# Detector.net
KiCad netlist of a schematic drawn in Altium Designer
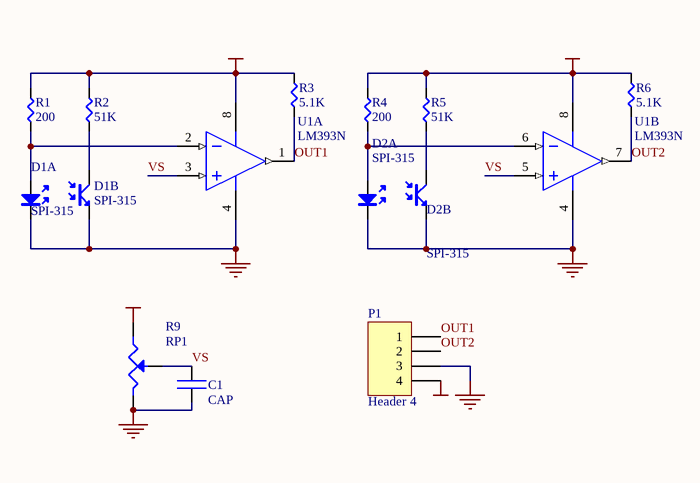
[diagram p0: Detector.SchDoc]

(export (version "E")
  (design (tool "Eeschema 10.0.6"))
  (components
    (comp (ref "C1") (value "CAP") (footprint "C0.1/0.2") (libsource (lib "Traffic_light") (part "CAP")))
    (comp (ref "D1")
      (value "SPI-315")
      (footprint "photodevice")
      (libsource (lib "Traffic_light") (part "PHOTOISO3"))
    )
    (comp (ref "D2")
      (value "SPI-315")
      (footprint "photodevice")
      (libsource (lib "Traffic_light") (part "PHOTOISO3"))
    )
    (comp (ref "P1")
      (value "Header 4")
      (footprint "HDR1X4")
      (description "Header, 4-Pin")
      (fields (field (name "PUBLISHER") "Altium Limited"))
      (libsource (lib "Miscellaneous Connectors") (part "Header 4"))
    )
    (comp (ref "R1") (value "200") (footprint "AXIAL0.4") (libsource (lib "Traffic_light") (part "R1")))
    (comp (ref "R2") (value "51K") (footprint "AXIAL0.4") (libsource (lib "Traffic_light") (part "R1")))
    (comp (ref "R3") (value "5.1K") (footprint "AXIAL0.4") (libsource (lib "Traffic_light") (part "R1")))
    (comp (ref "R4") (value "200") (footprint "AXIAL0.4") (libsource (lib "Traffic_light") (part "R1")))
    (comp (ref "R5") (value "51K") (footprint "AXIAL0.4") (libsource (lib "Traffic_light") (part "R1")))
    (comp (ref "R6") (value "5.1K") (footprint "AXIAL0.4") (libsource (lib "Traffic_light") (part "R1")))
    (comp (ref "R9")
      (value "RP1")
      (footprint "RP_05")
      (description "Potentiometer")
      (libsource (lib "Traffic_light") (part "RP1"))
    )
    (comp (ref "U1")
      (value "LM393N")
      (footprint "626-05")
      (description "Dual Comparator")
      (fields (field (name "PUBLISHER") "Altium Limited"))
      (libsource (lib "Motorola Analog Comparator") (part "LM393N"))
    )
  )
  (nets
    (net (code "1") (name "/OUT1") (class "Default")
      (node (ref "P1") (pin "1") (pinfunction "1_1") (pintype "passive"))
      (node (ref "R3") (pin "1") (pintype "passive"))
      (node (ref "U1") (pin "1") (pinfunction "OUT_1") (pintype "output"))
    )
    (net (code "2") (name "/OUT2") (class "Default")
      (node (ref "P1") (pin "2") (pinfunction "2_2") (pintype "passive"))
      (node (ref "R6") (pin "1") (pintype "passive"))
      (node (ref "U1") (pin "7") (pinfunction "OUT_7") (pintype "output"))
    )
    (net (code "3") (name "/VS") (class "Default")
      (node (ref "C1") (pin "1") (pintype "passive"))
      (node (ref "R9") (pin "2") (pinfunction "W_2") (pintype "passive"))
      (node (ref "U1") (pin "3") (pinfunction "IN+_3") (pintype "input"))
      (node (ref "U1") (pin "5") (pinfunction "IN+_5") (pintype "input"))
    )
    (net (code "4") (name "GND") (class "Default")
      (node (ref "C1") (pin "2") (pintype "passive"))
      (node (ref "D1") (pin "2") (pintype "passive"))
      (node (ref "D1") (pin "4") (pintype "passive"))
      (node (ref "D2") (pin "2") (pintype "passive"))
      (node (ref "D2") (pin "4") (pintype "passive"))
      (node (ref "P1") (pin "3") (pinfunction "3_3") (pintype "passive"))
      (node (ref "R9") (pin "1") (pinfunction "1_1") (pintype "passive"))
      (node (ref "U1") (pin "4") (pinfunction "GND_4") (pintype "power_in"))
    )
    (net (code "5") (name "Net-(D1-Pad3)") (class "Default")
      (node (ref "D1") (pin "3") (pintype "passive"))
      (node (ref "R2") (pin "1") (pintype "passive"))
    )
    (net (code "6") (name "Net-(D2-Pad3)") (class "Default")
      (node (ref "D2") (pin "3") (pintype "passive"))
      (node (ref "R5") (pin "1") (pintype "passive"))
    )
    (net (code "7") (name "Net-(U1A-IN-)") (class "Default")
      (node (ref "D1") (pin "1") (pintype "passive"))
      (node (ref "R1") (pin "1") (pintype "passive"))
      (node (ref "U1") (pin "2") (pinfunction "IN-_2") (pintype "input"))
    )
    (net (code "8") (name "Net-(U1B-IN-)") (class "Default")
      (node (ref "D2") (pin "1") (pintype "passive"))
      (node (ref "R4") (pin "1") (pintype "passive"))
      (node (ref "U1") (pin "6") (pinfunction "IN-_6") (pintype "input"))
    )
    (net (code "9") (name "VCC") (class "Default")
      (node (ref "P1") (pin "4") (pinfunction "4_4") (pintype "passive"))
      (node (ref "R1") (pin "2") (pintype "passive"))
      (node (ref "R2") (pin "2") (pintype "passive"))
      (node (ref "R3") (pin "2") (pintype "passive"))
      (node (ref "R4") (pin "2") (pintype "passive"))
      (node (ref "R5") (pin "2") (pintype "passive"))
      (node (ref "R6") (pin "2") (pintype "passive"))
      (node (ref "R9") (pin "3") (pinfunction "2_3") (pintype "passive"))
      (node (ref "U1") (pin "8") (pinfunction "V+_8") (pintype "power_in"))
    )
  )
)
